# FPGA1.net
KiCad netlist of a schematic drawn in Altium Designer
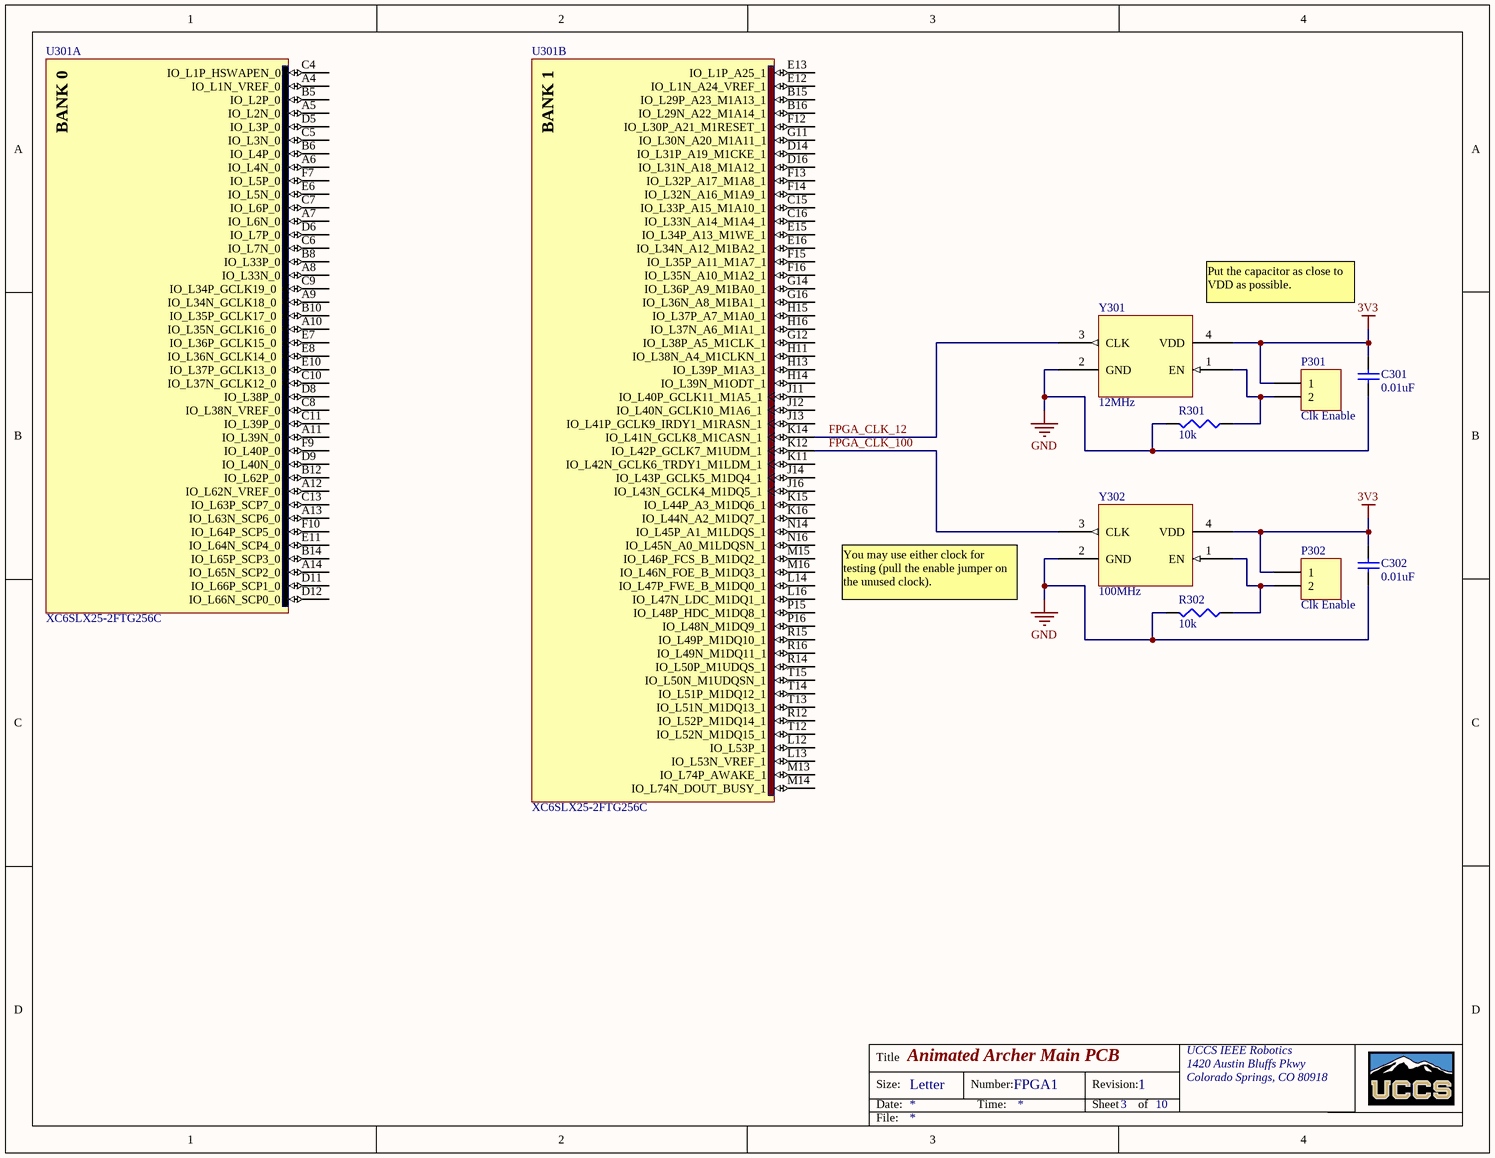
[diagram p0: FPGA1.SchDoc]

(export (version "E")
  (design (tool "Eeschema 10.0.6"))
  (components
    (comp (ref "C301")
      (value "0.01uF")
      (footprint "1608[0603]")
      (description "Capacitor (Semiconductor SIM Model)")
      (fields (field (name "Comment") "Cap Semi") (field (name "PUBLISHER") "Altium Limited"))
      (libsource (lib "Miscellaneous Devices") (part "Cap Semi"))
    )
    (comp (ref "C302")
      (value "0.01uF")
      (footprint "1608[0603]")
      (description "Capacitor (Semiconductor SIM Model)")
      (fields (field (name "Comment") "Cap Semi") (field (name "PUBLISHER") "Altium Limited"))
      (libsource (lib "Miscellaneous Devices") (part "Cap Semi"))
    )
    (comp (ref "P301")
      (value "Clk Enable")
      (footprint "HDR1X2")
      (description "Header, 2-Pin")
      (fields (field (name "PUBLISHER") "Altium Limited"))
      (libsource (lib "Miscellaneous Connectors") (part "Header 2"))
    )
    (comp (ref "P302")
      (value "Clk Enable")
      (footprint "HDR1X2")
      (description "Header, 2-Pin")
      (fields (field (name "PUBLISHER") "Altium Limited"))
      (libsource (lib "Miscellaneous Connectors") (part "Header 2"))
    )
    (comp (ref "R301")
      (value "10k")
      (footprint "J1-0603")
      (description "Resistor")
      (fields (field (name "Comment") "Res3") (field (name "PUBLISHER") "Altium Limited"))
      (libsource (lib "Miscellaneous Devices") (part "Res3"))
    )
    (comp (ref "R302")
      (value "10k")
      (footprint "J1-0603")
      (description "Resistor")
      (fields (field (name "Comment") "Res3") (field (name "PUBLISHER") "Altium Limited"))
      (libsource (lib "Miscellaneous Devices") (part "Res3"))
    )
    (comp (ref "U301")
      (value "XC6SLX25-2FTG256C")
      (footprint "FTG256")
      (fields (field (name "PUBLISHER") "Altium Limited"))
      (libsource (lib "Animated Archer") (part "XC6SLX25-2FTG256C"))
    )
    (comp (ref "Y301")
      (value "12MHz")
      (footprint "ASFLMB")
      (description "ASFLMB Clock Oscillator")
      (libsource (lib "Image Vortex Rev4") (part "ASFLMB"))
    )
    (comp (ref "Y302")
      (value "100MHz")
      (footprint "ASFLMB")
      (description "ASFLMB Clock Oscillator")
      (libsource (lib "Image Vortex Rev4") (part "ASFLMB"))
    )
  )
  (nets
    (net (code "1") (name "/FPGA_CLK_12") (class "Default")
      (node (ref "U301") (pin "K14") (pinfunction "IO_L41N_GCLK8_M1CASN_1_K14") (pintype "bidirectional"))
      (node (ref "Y301") (pin "3") (pinfunction "CLK_3") (pintype "output"))
    )
    (net (code "2") (name "/FPGA_CLK_100") (class "Default")
      (node (ref "U301") (pin "K12") (pinfunction "IO_L42P_GCLK7_M1UDM_1_K12") (pintype "bidirectional"))
      (node (ref "Y302") (pin "3") (pinfunction "CLK_3") (pintype "output"))
    )
    (net (code "3") (name "3V3") (class "Default")
      (node (ref "C301") (pin "2") (pinfunction "2_2") (pintype "passive"))
      (node (ref "C302") (pin "2") (pinfunction "2_2") (pintype "passive"))
      (node (ref "P301") (pin "1") (pinfunction "1_1") (pintype "passive"))
      (node (ref "P302") (pin "1") (pinfunction "1_1") (pintype "passive"))
      (node (ref "Y301") (pin "4") (pinfunction "VDD_4") (pintype "power_in"))
      (node (ref "Y302") (pin "4") (pinfunction "VDD_4") (pintype "power_in"))
    )
    (net (code "4") (name "GND") (class "Default")
      (node (ref "C301") (pin "1") (pinfunction "1_1") (pintype "passive"))
      (node (ref "C302") (pin "1") (pinfunction "1_1") (pintype "passive"))
      (node (ref "R301") (pin "2") (pinfunction "2_2") (pintype "passive"))
      (node (ref "R302") (pin "2") (pinfunction "2_2") (pintype "passive"))
      (node (ref "Y301") (pin "2") (pinfunction "GND_2") (pintype "power_in"))
      (node (ref "Y302") (pin "2") (pinfunction "GND_2") (pintype "power_in"))
    )
    (net (code "5") (name "Net-(Y301-EN)") (class "Default")
      (node (ref "P301") (pin "2") (pinfunction "2_2") (pintype "passive"))
      (node (ref "R301") (pin "1") (pinfunction "1_1") (pintype "passive"))
      (node (ref "Y301") (pin "1") (pinfunction "EN_1") (pintype "input"))
    )
    (net (code "6") (name "Net-(Y302-EN)") (class "Default")
      (node (ref "P302") (pin "2") (pinfunction "2_2") (pintype "passive"))
      (node (ref "R302") (pin "1") (pinfunction "1_1") (pintype "passive"))
      (node (ref "Y302") (pin "1") (pinfunction "EN_1") (pintype "input"))
    )
    (net (code "7") (name "unconnected-(U301A-IO_L1N_VREF_0-PadA4)") (class "Default")
      (node (ref "U301") (pin "A4") (pinfunction "IO_L1N_VREF_0_A4") (pintype "bidirectional"))
    )
    (net (code "8") (name "unconnected-(U301A-IO_L1P_HSWAPEN_0-PadC4)") (class "Default")
      (node (ref "U301") (pin "C4") (pinfunction "IO_L1P_HSWAPEN_0_C4") (pintype "bidirectional"))
    )
    (net (code "9") (name "unconnected-(U301A-IO_L2N_0-PadA5)") (class "Default")
      (node (ref "U301") (pin "A5") (pinfunction "IO_L2N_0_A5") (pintype "bidirectional"))
    )
    (net (code "10") (name "unconnected-(U301A-IO_L2P_0-PadB5)") (class "Default")
      (node (ref "U301") (pin "B5") (pinfunction "IO_L2P_0_B5") (pintype "bidirectional"))
    )
    (net (code "11") (name "unconnected-(U301A-IO_L3N_0-PadC5)") (class "Default")
      (node (ref "U301") (pin "C5") (pinfunction "IO_L3N_0_C5") (pintype "bidirectional"))
    )
    (net (code "12") (name "unconnected-(U301A-IO_L3P_0-PadD5)") (class "Default")
      (node (ref "U301") (pin "D5") (pinfunction "IO_L3P_0_D5") (pintype "bidirectional"))
    )
    (net (code "13") (name "unconnected-(U301A-IO_L4N_0-PadA6)") (class "Default")
      (node (ref "U301") (pin "A6") (pinfunction "IO_L4N_0_A6") (pintype "bidirectional"))
    )
    (net (code "14") (name "unconnected-(U301A-IO_L4P_0-PadB6)") (class "Default")
      (node (ref "U301") (pin "B6") (pinfunction "IO_L4P_0_B6") (pintype "bidirectional"))
    )
    (net (code "15") (name "unconnected-(U301A-IO_L5N_0-PadE6)") (class "Default")
      (node (ref "U301") (pin "E6") (pinfunction "IO_L5N_0_E6") (pintype "bidirectional"))
    )
    (net (code "16") (name "unconnected-(U301A-IO_L5P_0-PadF7)") (class "Default")
      (node (ref "U301") (pin "F7") (pinfunction "IO_L5P_0_F7") (pintype "bidirectional"))
    )
    (net (code "17") (name "unconnected-(U301A-IO_L6N_0-PadA7)") (class "Default")
      (node (ref "U301") (pin "A7") (pinfunction "IO_L6N_0_A7") (pintype "bidirectional"))
    )
    (net (code "18") (name "unconnected-(U301A-IO_L6P_0-PadC7)") (class "Default")
      (node (ref "U301") (pin "C7") (pinfunction "IO_L6P_0_C7") (pintype "bidirectional"))
    )
    (net (code "19") (name "unconnected-(U301A-IO_L7N_0-PadC6)") (class "Default")
      (node (ref "U301") (pin "C6") (pinfunction "IO_L7N_0_C6") (pintype "bidirectional"))
    )
    (net (code "20") (name "unconnected-(U301A-IO_L7P_0-PadD6)") (class "Default")
      (node (ref "U301") (pin "D6") (pinfunction "IO_L7P_0_D6") (pintype "bidirectional"))
    )
    (net (code "21") (name "unconnected-(U301A-IO_L33N_0-PadA8)") (class "Default")
      (node (ref "U301") (pin "A8") (pinfunction "IO_L33N_0_A8") (pintype "bidirectional"))
    )
    (net (code "22") (name "unconnected-(U301A-IO_L33P_0-PadB8)") (class "Default")
      (node (ref "U301") (pin "B8") (pinfunction "IO_L33P_0_B8") (pintype "bidirectional"))
    )
    (net (code "23") (name "unconnected-(U301A-IO_L34N_GCLK18_0-PadA9)") (class "Default")
      (node (ref "U301") (pin "A9") (pinfunction "IO_L34N_GCLK18_0_A9") (pintype "bidirectional"))
    )
    (net (code "24") (name "unconnected-(U301A-IO_L34P_GCLK19_0-PadC9)") (class "Default")
      (node (ref "U301") (pin "C9") (pinfunction "IO_L34P_GCLK19_0_C9") (pintype "bidirectional"))
    )
    (net (code "25") (name "unconnected-(U301A-IO_L35N_GCLK16_0-PadA10)") (class "Default")
      (node (ref "U301") (pin "A10") (pinfunction "IO_L35N_GCLK16_0_A10") (pintype "bidirectional"))
    )
    (net (code "26") (name "unconnected-(U301A-IO_L35P_GCLK17_0-PadB10)") (class "Default")
      (node (ref "U301") (pin "B10") (pinfunction "IO_L35P_GCLK17_0_B10") (pintype "bidirectional"))
    )
    (net (code "27") (name "unconnected-(U301A-IO_L36N_GCLK14_0-PadE8)") (class "Default")
      (node (ref "U301") (pin "E8") (pinfunction "IO_L36N_GCLK14_0_E8") (pintype "bidirectional"))
    )
    (net (code "28") (name "unconnected-(U301A-IO_L36P_GCLK15_0-PadE7)") (class "Default")
      (node (ref "U301") (pin "E7") (pinfunction "IO_L36P_GCLK15_0_E7") (pintype "bidirectional"))
    )
    (net (code "29") (name "unconnected-(U301A-IO_L37N_GCLK12_0-PadC10)") (class "Default")
      (node (ref "U301") (pin "C10") (pinfunction "IO_L37N_GCLK12_0_C10") (pintype "bidirectional"))
    )
    (net (code "30") (name "unconnected-(U301A-IO_L37P_GCLK13_0-PadE10)") (class "Default")
      (node (ref "U301") (pin "E10") (pinfunction "IO_L37P_GCLK13_0_E10") (pintype "bidirectional"))
    )
    (net (code "31") (name "unconnected-(U301A-IO_L38N_VREF_0-PadC8)") (class "Default")
      (node (ref "U301") (pin "C8") (pinfunction "IO_L38N_VREF_0_C8") (pintype "bidirectional"))
    )
    (net (code "32") (name "unconnected-(U301A-IO_L38P_0-PadD8)") (class "Default")
      (node (ref "U301") (pin "D8") (pinfunction "IO_L38P_0_D8") (pintype "bidirectional"))
    )
    (net (code "33") (name "unconnected-(U301A-IO_L39N_0-PadA11)") (class "Default")
      (node (ref "U301") (pin "A11") (pinfunction "IO_L39N_0_A11") (pintype "bidirectional"))
    )
    (net (code "34") (name "unconnected-(U301A-IO_L39P_0-PadC11)") (class "Default")
      (node (ref "U301") (pin "C11") (pinfunction "IO_L39P_0_C11") (pintype "bidirectional"))
    )
    (net (code "35") (name "unconnected-(U301A-IO_L40N_0-PadD9)") (class "Default")
      (node (ref "U301") (pin "D9") (pinfunction "IO_L40N_0_D9") (pintype "bidirectional"))
    )
    (net (code "36") (name "unconnected-(U301A-IO_L40P_0-PadF9)") (class "Default")
      (node (ref "U301") (pin "F9") (pinfunction "IO_L40P_0_F9") (pintype "bidirectional"))
    )
    (net (code "37") (name "unconnected-(U301A-IO_L62N_VREF_0-PadA12)") (class "Default")
      (node (ref "U301") (pin "A12") (pinfunction "IO_L62N_VREF_0_A12") (pintype "bidirectional"))
    )
    (net (code "38") (name "unconnected-(U301A-IO_L62P_0-PadB12)") (class "Default")
      (node (ref "U301") (pin "B12") (pinfunction "IO_L62P_0_B12") (pintype "bidirectional"))
    )
    (net (code "39") (name "unconnected-(U301A-IO_L63N_SCP6_0-PadA13)") (class "Default")
      (node (ref "U301") (pin "A13") (pinfunction "IO_L63N_SCP6_0_A13") (pintype "bidirectional"))
    )
    (net (code "40") (name "unconnected-(U301A-IO_L63P_SCP7_0-PadC13)") (class "Default")
      (node (ref "U301") (pin "C13") (pinfunction "IO_L63P_SCP7_0_C13") (pintype "bidirectional"))
    )
    (net (code "41") (name "unconnected-(U301A-IO_L64N_SCP4_0-PadE11)") (class "Default")
      (node (ref "U301") (pin "E11") (pinfunction "IO_L64N_SCP4_0_E11") (pintype "bidirectional"))
    )
    (net (code "42") (name "unconnected-(U301A-IO_L64P_SCP5_0-PadF10)") (class "Default")
      (node (ref "U301") (pin "F10") (pinfunction "IO_L64P_SCP5_0_F10") (pintype "bidirectional"))
    )
    (net (code "43") (name "unconnected-(U301A-IO_L65N_SCP2_0-PadA14)") (class "Default")
      (node (ref "U301") (pin "A14") (pinfunction "IO_L65N_SCP2_0_A14") (pintype "bidirectional"))
    )
    (net (code "44") (name "unconnected-(U301A-IO_L65P_SCP3_0-PadB14)") (class "Default")
      (node (ref "U301") (pin "B14") (pinfunction "IO_L65P_SCP3_0_B14") (pintype "bidirectional"))
    )
    (net (code "45") (name "unconnected-(U301A-IO_L66N_SCP0_0-PadD12)") (class "Default")
      (node (ref "U301") (pin "D12") (pinfunction "IO_L66N_SCP0_0_D12") (pintype "bidirectional"))
    )
    (net (code "46") (name "unconnected-(U301A-IO_L66P_SCP1_0-PadD11)") (class "Default")
      (node (ref "U301") (pin "D11") (pinfunction "IO_L66P_SCP1_0_D11") (pintype "bidirectional"))
    )
    (net (code "47") (name "unconnected-(U301B-IO_L1N_A24_VREF_1-PadE12)") (class "Default")
      (node (ref "U301") (pin "E12") (pinfunction "IO_L1N_A24_VREF_1_E12") (pintype "bidirectional"))
    )
    (net (code "48") (name "unconnected-(U301B-IO_L1P_A25_1-PadE13)") (class "Default")
      (node (ref "U301") (pin "E13") (pinfunction "IO_L1P_A25_1_E13") (pintype "bidirectional"))
    )
    (net (code "49") (name "unconnected-(U301B-IO_L29N_A22_M1A14_1-PadB16)") (class "Default")
      (node (ref "U301") (pin "B16") (pinfunction "IO_L29N_A22_M1A14_1_B16") (pintype "bidirectional"))
    )
    (net (code "50") (name "unconnected-(U301B-IO_L29P_A23_M1A13_1-PadB15)") (class "Default")
      (node (ref "U301") (pin "B15") (pinfunction "IO_L29P_A23_M1A13_1_B15") (pintype "bidirectional"))
    )
    (net (code "51") (name "unconnected-(U301B-IO_L30N_A20_M1A11_1-PadG11)") (class "Default")
      (node (ref "U301") (pin "G11") (pinfunction "IO_L30N_A20_M1A11_1_G11") (pintype "bidirectional"))
    )
    (net (code "52") (name "unconnected-(U301B-IO_L30P_A21_M1RESET_1-PadF12)") (class "Default")
      (node (ref "U301") (pin "F12") (pinfunction "IO_L30P_A21_M1RESET_1_F12") (pintype "bidirectional"))
    )
    (net (code "53") (name "unconnected-(U301B-IO_L31N_A18_M1A12_1-PadD16)") (class "Default")
      (node (ref "U301") (pin "D16") (pinfunction "IO_L31N_A18_M1A12_1_D16") (pintype "bidirectional"))
    )
    (net (code "54") (name "unconnected-(U301B-IO_L31P_A19_M1CKE_1-PadD14)") (class "Default")
      (node (ref "U301") (pin "D14") (pinfunction "IO_L31P_A19_M1CKE_1_D14") (pintype "bidirectional"))
    )
    (net (code "55") (name "unconnected-(U301B-IO_L32N_A16_M1A9_1-PadF14)") (class "Default")
      (node (ref "U301") (pin "F14") (pinfunction "IO_L32N_A16_M1A9_1_F14") (pintype "bidirectional"))
    )
    (net (code "56") (name "unconnected-(U301B-IO_L32P_A17_M1A8_1-PadF13)") (class "Default")
      (node (ref "U301") (pin "F13") (pinfunction "IO_L32P_A17_M1A8_1_F13") (pintype "bidirectional"))
    )
    (net (code "57") (name "unconnected-(U301B-IO_L33N_A14_M1A4_1-PadC16)") (class "Default")
      (node (ref "U301") (pin "C16") (pinfunction "IO_L33N_A14_M1A4_1_C16") (pintype "bidirectional"))
    )
    (net (code "58") (name "unconnected-(U301B-IO_L33P_A15_M1A10_1-PadC15)") (class "Default")
      (node (ref "U301") (pin "C15") (pinfunction "IO_L33P_A15_M1A10_1_C15") (pintype "bidirectional"))
    )
    (net (code "59") (name "unconnected-(U301B-IO_L34N_A12_M1BA2_1-PadE16)") (class "Default")
      (node (ref "U301") (pin "E16") (pinfunction "IO_L34N_A12_M1BA2_1_E16") (pintype "bidirectional"))
    )
    (net (code "60") (name "unconnected-(U301B-IO_L34P_A13_M1WE_1-PadE15)") (class "Default")
      (node (ref "U301") (pin "E15") (pinfunction "IO_L34P_A13_M1WE_1_E15") (pintype "bidirectional"))
    )
    (net (code "61") (name "unconnected-(U301B-IO_L35N_A10_M1A2_1-PadF16)") (class "Default")
      (node (ref "U301") (pin "F16") (pinfunction "IO_L35N_A10_M1A2_1_F16") (pintype "bidirectional"))
    )
    (net (code "62") (name "unconnected-(U301B-IO_L35P_A11_M1A7_1-PadF15)") (class "Default")
      (node (ref "U301") (pin "F15") (pinfunction "IO_L35P_A11_M1A7_1_F15") (pintype "bidirectional"))
    )
    (net (code "63") (name "unconnected-(U301B-IO_L36N_A8_M1BA1_1-PadG16)") (class "Default")
      (node (ref "U301") (pin "G16") (pinfunction "IO_L36N_A8_M1BA1_1_G16") (pintype "bidirectional"))
    )
    (net (code "64") (name "unconnected-(U301B-IO_L36P_A9_M1BA0_1-PadG14)") (class "Default")
      (node (ref "U301") (pin "G14") (pinfunction "IO_L36P_A9_M1BA0_1_G14") (pintype "bidirectional"))
    )
    (net (code "65") (name "unconnected-(U301B-IO_L37N_A6_M1A1_1-PadH16)") (class "Default")
      (node (ref "U301") (pin "H16") (pinfunction "IO_L37N_A6_M1A1_1_H16") (pintype "bidirectional"))
    )
    (net (code "66") (name "unconnected-(U301B-IO_L37P_A7_M1A0_1-PadH15)") (class "Default")
      (node (ref "U301") (pin "H15") (pinfunction "IO_L37P_A7_M1A0_1_H15") (pintype "bidirectional"))
    )
    (net (code "67") (name "unconnected-(U301B-IO_L38N_A4_M1CLKN_1-PadH11)") (class "Default")
      (node (ref "U301") (pin "H11") (pinfunction "IO_L38N_A4_M1CLKN_1_H11") (pintype "bidirectional"))
    )
    (net (code "68") (name "unconnected-(U301B-IO_L38P_A5_M1CLK_1-PadG12)") (class "Default")
      (node (ref "U301") (pin "G12") (pinfunction "IO_L38P_A5_M1CLK_1_G12") (pintype "bidirectional"))
    )
    (net (code "69") (name "unconnected-(U301B-IO_L39N_M1ODT_1-PadH14)") (class "Default")
      (node (ref "U301") (pin "H14") (pinfunction "IO_L39N_M1ODT_1_H14") (pintype "bidirectional"))
    )
    (net (code "70") (name "unconnected-(U301B-IO_L39P_M1A3_1-PadH13)") (class "Default")
      (node (ref "U301") (pin "H13") (pinfunction "IO_L39P_M1A3_1_H13") (pintype "bidirectional"))
    )
    (net (code "71") (name "unconnected-(U301B-IO_L40N_GCLK10_M1A6_1-PadJ12)") (class "Default")
      (node (ref "U301") (pin "J12") (pinfunction "IO_L40N_GCLK10_M1A6_1_J12") (pintype "bidirectional"))
    )
    (net (code "72") (name "unconnected-(U301B-IO_L40P_GCLK11_M1A5_1-PadJ11)") (class "Default")
      (node (ref "U301") (pin "J11") (pinfunction "IO_L40P_GCLK11_M1A5_1_J11") (pintype "bidirectional"))
    )
    (net (code "73") (name "unconnected-(U301B-IO_L41P_GCLK9_IRDY1_M1RASN_1-PadJ13)") (class "Default")
      (node (ref "U301") (pin "J13") (pinfunction "IO_L41P_GCLK9_IRDY1_M1RASN_1_J13") (pintype "bidirectional"))
    )
    (net (code "74") (name "unconnected-(U301B-IO_L42N_GCLK6_TRDY1_M1LDM_1-PadK11)") (class "Default")
      (node (ref "U301") (pin "K11") (pinfunction "IO_L42N_GCLK6_TRDY1_M1LDM_1_K11") (pintype "bidirectional"))
    )
    (net (code "75") (name "unconnected-(U301B-IO_L43N_GCLK4_M1DQ5_1-PadJ16)") (class "Default")
      (node (ref "U301") (pin "J16") (pinfunction "IO_L43N_GCLK4_M1DQ5_1_J16") (pintype "bidirectional"))
    )
    (net (code "76") (name "unconnected-(U301B-IO_L43P_GCLK5_M1DQ4_1-PadJ14)") (class "Default")
      (node (ref "U301") (pin "J14") (pinfunction "IO_L43P_GCLK5_M1DQ4_1_J14") (pintype "bidirectional"))
    )
    (net (code "77") (name "unconnected-(U301B-IO_L44N_A2_M1DQ7_1-PadK16)") (class "Default")
      (node (ref "U301") (pin "K16") (pinfunction "IO_L44N_A2_M1DQ7_1_K16") (pintype "bidirectional"))
    )
    (net (code "78") (name "unconnected-(U301B-IO_L44P_A3_M1DQ6_1-PadK15)") (class "Default")
      (node (ref "U301") (pin "K15") (pinfunction "IO_L44P_A3_M1DQ6_1_K15") (pintype "bidirectional"))
    )
    (net (code "79") (name "unconnected-(U301B-IO_L45N_A0_M1LDQSN_1-PadN16)") (class "Default")
      (node (ref "U301") (pin "N16") (pinfunction "IO_L45N_A0_M1LDQSN_1_N16") (pintype "bidirectional"))
    )
    (net (code "80") (name "unconnected-(U301B-IO_L45P_A1_M1LDQS_1-PadN14)") (class "Default")
      (node (ref "U301") (pin "N14") (pinfunction "IO_L45P_A1_M1LDQS_1_N14") (pintype "bidirectional"))
    )
    (net (code "81") (name "unconnected-(U301B-IO_L46N_FOE_B_M1DQ3_1-PadM16)") (class "Default")
      (node (ref "U301") (pin "M16") (pinfunction "IO_L46N_FOE_B_M1DQ3_1_M16") (pintype "bidirectional"))
    )
    (net (code "82") (name "unconnected-(U301B-IO_L46P_FCS_B_M1DQ2_1-PadM15)") (class "Default")
      (node (ref "U301") (pin "M15") (pinfunction "IO_L46P_FCS_B_M1DQ2_1_M15") (pintype "bidirectional"))
    )
    (net (code "83") (name "unconnected-(U301B-IO_L47N_LDC_M1DQ1_1-PadL16)") (class "Default")
      (node (ref "U301") (pin "L16") (pinfunction "IO_L47N_LDC_M1DQ1_1_L16") (pintype "bidirectional"))
    )
    (net (code "84") (name "unconnected-(U301B-IO_L47P_FWE_B_M1DQ0_1-PadL14)") (class "Default")
      (node (ref "U301") (pin "L14") (pinfunction "IO_L47P_FWE_B_M1DQ0_1_L14") (pintype "bidirectional"))
    )
    (net (code "85") (name "unconnected-(U301B-IO_L48N_M1DQ9_1-PadP16)") (class "Default")
      (node (ref "U301") (pin "P16") (pinfunction "IO_L48N_M1DQ9_1_P16") (pintype "bidirectional"))
    )
    (net (code "86") (name "unconnected-(U301B-IO_L48P_HDC_M1DQ8_1-PadP15)") (class "Default")
      (node (ref "U301") (pin "P15") (pinfunction "IO_L48P_HDC_M1DQ8_1_P15") (pintype "bidirectional"))
    )
    (net (code "87") (name "unconnected-(U301B-IO_L49N_M1DQ11_1-PadR16)") (class "Default")
      (node (ref "U301") (pin "R16") (pinfunction "IO_L49N_M1DQ11_1_R16") (pintype "bidirectional"))
    )
    (net (code "88") (name "unconnected-(U301B-IO_L49P_M1DQ10_1-PadR15)") (class "Default")
      (node (ref "U301") (pin "R15") (pinfunction "IO_L49P_M1DQ10_1_R15") (pintype "bidirectional"))
    )
    (net (code "89") (name "unconnected-(U301B-IO_L50N_M1UDQSN_1-PadT15)") (class "Default")
      (node (ref "U301") (pin "T15") (pinfunction "IO_L50N_M1UDQSN_1_T15") (pintype "bidirectional"))
    )
    (net (code "90") (name "unconnected-(U301B-IO_L50P_M1UDQS_1-PadR14)") (class "Default")
      (node (ref "U301") (pin "R14") (pinfunction "IO_L50P_M1UDQS_1_R14") (pintype "bidirectional"))
    )
    (net (code "91") (name "unconnected-(U301B-IO_L51N_M1DQ13_1-PadT13)") (class "Default")
      (node (ref "U301") (pin "T13") (pinfunction "IO_L51N_M1DQ13_1_T13") (pintype "bidirectional"))
    )
    (net (code "92") (name "unconnected-(U301B-IO_L51P_M1DQ12_1-PadT14)") (class "Default")
      (node (ref "U301") (pin "T14") (pinfunction "IO_L51P_M1DQ12_1_T14") (pintype "bidirectional"))
    )
    (net (code "93") (name "unconnected-(U301B-IO_L52N_M1DQ15_1-PadT12)") (class "Default")
      (node (ref "U301") (pin "T12") (pinfunction "IO_L52N_M1DQ15_1_T12") (pintype "bidirectional"))
    )
    (net (code "94") (name "unconnected-(U301B-IO_L52P_M1DQ14_1-PadR12)") (class "Default")
      (node (ref "U301") (pin "R12") (pinfunction "IO_L52P_M1DQ14_1_R12") (pintype "bidirectional"))
    )
    (net (code "95") (name "unconnected-(U301B-IO_L53N_VREF_1-PadL13)") (class "Default")
      (node (ref "U301") (pin "L13") (pinfunction "IO_L53N_VREF_1_L13") (pintype "bidirectional"))
    )
    (net (code "96") (name "unconnected-(U301B-IO_L53P_1-PadL12)") (class "Default")
      (node (ref "U301") (pin "L12") (pinfunction "IO_L53P_1_L12") (pintype "bidirectional"))
    )
    (net (code "97") (name "unconnected-(U301B-IO_L74N_DOUT_BUSY_1-PadM14)") (class "Default")
      (node (ref "U301") (pin "M14") (pinfunction "IO_L74N_DOUT_BUSY_1_M14") (pintype "bidirectional"))
    )
    (net (code "98") (name "unconnected-(U301B-IO_L74P_AWAKE_1-PadM13)") (class "Default")
      (node (ref "U301") (pin "M13") (pinfunction "IO_L74P_AWAKE_1_M13") (pintype "bidirectional"))
    )
  )
)
